# Touch.net
KiCad netlist of a schematic drawn in Altium Designer
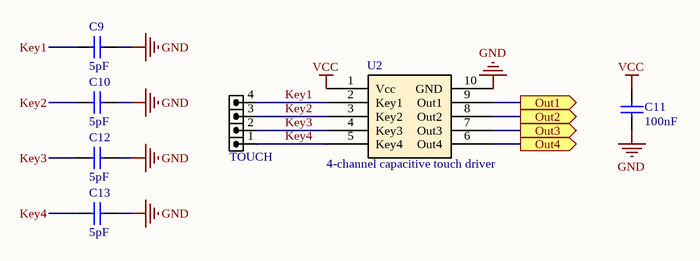
[diagram p0: Touch.SchDoc]

(export (version "E")
  (design (tool "Eeschema 10.0.6"))
  (components
    (comp (ref "C9")
      (value "5pF")
      (footprint "0603C")
      (description "Capacitor")
      (libsource (lib "NAHAL_LIB") (part "Cap"))
    )
    (comp (ref "C10")
      (value "5pF")
      (footprint "0603C")
      (description "Capacitor")
      (libsource (lib "NAHAL_LIB") (part "Cap"))
    )
    (comp (ref "C11")
      (value "100nF")
      (footprint "0603C")
      (description "Capacitor")
      (libsource (lib "NAHAL_LIB") (part "Cap"))
    )
    (comp (ref "C12")
      (value "5pF")
      (footprint "0603C")
      (description "Capacitor")
      (libsource (lib "NAHAL_LIB") (part "Cap"))
    )
    (comp (ref "C13")
      (value "5pF")
      (footprint "0603C")
      (description "Capacitor")
      (libsource (lib "NAHAL_LIB") (part "Cap"))
    )
    (comp (ref "TOUCH")
      (value "HDR4")
      (footprint "HDR1SE_M_1X4")
      (description "HEADER, 1mm pitch, test, SMD")
      (libsource (lib "Conn Header") (part "HDRTST_1X4"))
    )
    (comp (ref "U2")
      (value "4-channel capacitive touch driver")
      (footprint "MSOP-10")
      (libsource (lib "Salman_lib") (part "BS814A-1"))
    )
  )
  (nets
    (net (code "1") (name "/Key1") (class "Default")
      (node (ref "C9") (pin "2") (pinfunction "2_2") (pintype "passive"))
      (node (ref "TOUCH") (pin "4") (pinfunction "4_4") (pintype "passive"))
      (node (ref "U2") (pin "2") (pinfunction "Key1_2") (pintype "passive"))
    )
    (net (code "2") (name "/Key2") (class "Default")
      (node (ref "C10") (pin "2") (pinfunction "2_2") (pintype "passive"))
      (node (ref "TOUCH") (pin "3") (pinfunction "3_3") (pintype "passive"))
      (node (ref "U2") (pin "3") (pinfunction "Key2_3") (pintype "passive"))
    )
    (net (code "3") (name "/Key3") (class "Default")
      (node (ref "C12") (pin "2") (pinfunction "2_2") (pintype "passive"))
      (node (ref "TOUCH") (pin "2") (pinfunction "2_2") (pintype "passive"))
      (node (ref "U2") (pin "4") (pinfunction "Key3_4") (pintype "passive"))
    )
    (net (code "4") (name "/Key4") (class "Default")
      (node (ref "C13") (pin "2") (pinfunction "2_2") (pintype "passive"))
      (node (ref "TOUCH") (pin "1") (pinfunction "1_1") (pintype "passive"))
      (node (ref "U2") (pin "5") (pinfunction "Key4_5") (pintype "passive"))
    )
    (net (code "5") (name "/Out1") (class "Default")
      (node (ref "U2") (pin "9") (pinfunction "Out1_9") (pintype "passive"))
    )
    (net (code "6") (name "/Out2") (class "Default")
      (node (ref "U2") (pin "8") (pinfunction "Out2_8") (pintype "passive"))
    )
    (net (code "7") (name "/Out3") (class "Default")
      (node (ref "U2") (pin "7") (pinfunction "Out3_7") (pintype "passive"))
    )
    (net (code "8") (name "/Out4") (class "Default")
      (node (ref "U2") (pin "6") (pinfunction "Out4_6") (pintype "passive"))
    )
    (net (code "9") (name "GND") (class "Default")
      (node (ref "C10") (pin "1") (pinfunction "1_1") (pintype "passive"))
      (node (ref "C11") (pin "1") (pinfunction "1_1") (pintype "passive"))
      (node (ref "C12") (pin "1") (pinfunction "1_1") (pintype "passive"))
      (node (ref "C13") (pin "1") (pinfunction "1_1") (pintype "passive"))
      (node (ref "C9") (pin "1") (pinfunction "1_1") (pintype "passive"))
      (node (ref "U2") (pin "10") (pinfunction "GND_10") (pintype "passive"))
    )
    (net (code "10") (name "VCC") (class "Default")
      (node (ref "C11") (pin "2") (pinfunction "2_2") (pintype "passive"))
      (node (ref "U2") (pin "1") (pinfunction "Vcc_1") (pintype "passive"))
    )
  )
)
